# micro_board.net
KiCad netlist of a schematic drawn in EAGLE
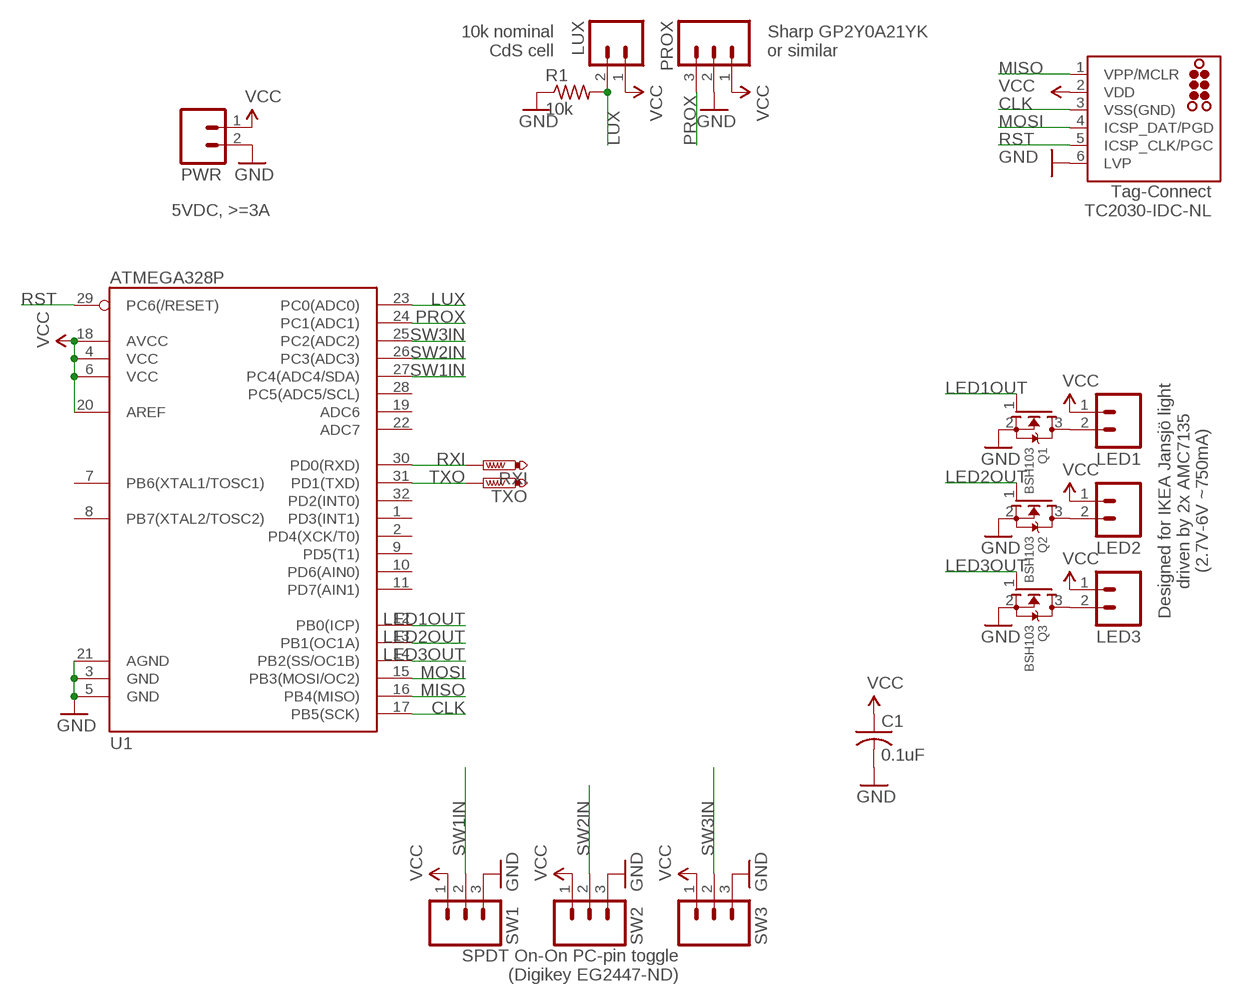
[diagram p0: schematic, sheet 1]

(export (version "E")
  (design (tool "Eeschema 10.0.6"))
  (components
    (comp (ref "C1")
      (value "0.1uF")
      (footprint "eagle-import:C0603")
      (libsource (lib "eagle-import") (part "C-USC0603"))
    )
    (comp (ref "J1")
      (value "TC2030-MCP-NL")
      (footprint "eagle-import:TC2030-MCP-NL")
      (libsource (lib "eagle-import") (part "TC2030-MCP-NL"))
    )
    (comp (ref "LED1")
      (value "M02POLAR_LOCK")
      (footprint "eagle-import:MOLEX-1X2_LOCK")
      (libsource (lib "eagle-import") (part "M02POLAR_LOCK"))
    )
    (comp (ref "LED2")
      (value "M02POLAR_LOCK")
      (footprint "eagle-import:MOLEX-1X2_LOCK")
      (libsource (lib "eagle-import") (part "M02POLAR_LOCK"))
    )
    (comp (ref "LED3")
      (value "M02POLAR_LOCK")
      (footprint "eagle-import:MOLEX-1X2_LOCK")
      (libsource (lib "eagle-import") (part "M02POLAR_LOCK"))
    )
    (comp (ref "LUX")
      (value "M02POLAR_LOCK")
      (footprint "eagle-import:MOLEX-1X2_LOCK")
      (libsource (lib "eagle-import") (part "M02POLAR_LOCK"))
    )
    (comp (ref "PROX")
      (value "M03POLAR_LOCK")
      (footprint "eagle-import:MOLEX-1X3_LOCK")
      (libsource (lib "eagle-import") (part "M03POLAR_LOCK"))
    )
    (comp (ref "PWR")
      (value "M02POLAR_LOCK")
      (footprint "eagle-import:MOLEX-1X2_LOCK")
      (libsource (lib "eagle-import") (part "M02POLAR_LOCK"))
    )
    (comp (ref "Q1")
      (value "BSH103")
      (footprint "eagle-import:SOT23")
      (libsource (lib "eagle-import") (part "MOSFET-NREFLOW"))
    )
    (comp (ref "Q2")
      (value "BSH103")
      (footprint "eagle-import:SOT23")
      (libsource (lib "eagle-import") (part "MOSFET-NREFLOW"))
    )
    (comp (ref "Q3")
      (value "BSH103")
      (footprint "eagle-import:SOT23")
      (libsource (lib "eagle-import") (part "MOSFET-NREFLOW"))
    )
    (comp (ref "R1")
      (value "10k")
      (footprint "eagle-import:R0603")
      (libsource (lib "eagle-import") (part "R-US_R0603"))
    )
    (comp (ref "RXI")
      (value "PTR1B1,27")
      (footprint "eagle-import:B1,27")
      (libsource (lib "eagle-import") (part "PTR1B1,27"))
    )
    (comp (ref "SW1")
      (value "M031X03_NO_SILK")
      (footprint "eagle-import:1X03_NO_SILK")
      (libsource (lib "eagle-import") (part "M031X03_NO_SILK"))
    )
    (comp (ref "SW2")
      (value "M031X03_NO_SILK")
      (footprint "eagle-import:1X03_NO_SILK")
      (libsource (lib "eagle-import") (part "M031X03_NO_SILK"))
    )
    (comp (ref "SW3")
      (value "M031X03_NO_SILK")
      (footprint "eagle-import:1X03_NO_SILK")
      (libsource (lib "eagle-import") (part "M031X03_NO_SILK"))
    )
    (comp (ref "TXO")
      (value "PTR1B1,27")
      (footprint "eagle-import:B1,27")
      (libsource (lib "eagle-import") (part "PTR1B1,27"))
    )
    (comp (ref "U1")
      (value "ATMEGA328P")
      (footprint "eagle-import:TQFP32-08")
      (libsource (lib "eagle-import") (part "ATMEGA328_SMT"))
    )
  )
  (nets
    (net (code "1") (name "/CLK") (class "Default")
      (node (ref "J1") (pin "3") (pinfunction "VSS(GND)_3") (pintype "power_in"))
      (node (ref "U1") (pin "17") (pinfunction "PB5(SCK)_17") (pintype "bidirectional"))
    )
    (net (code "2") (name "/LED1OUT") (class "Default")
      (node (ref "Q1") (pin "1") (pinfunction "G_1") (pintype "bidirectional"))
      (node (ref "U1") (pin "12") (pinfunction "PB0(ICP)_12") (pintype "bidirectional"))
    )
    (net (code "3") (name "/LED2OUT") (class "Default")
      (node (ref "Q2") (pin "1") (pinfunction "G_1") (pintype "bidirectional"))
      (node (ref "U1") (pin "13") (pinfunction "PB1(OC1A)_13") (pintype "bidirectional"))
    )
    (net (code "4") (name "/LED3OUT") (class "Default")
      (node (ref "Q3") (pin "1") (pinfunction "G_1") (pintype "bidirectional"))
      (node (ref "U1") (pin "14") (pinfunction "PB2(SS/OC1B)_14") (pintype "bidirectional"))
    )
    (net (code "5") (name "/LUX") (class "Default")
      (node (ref "LUX") (pin "2") (pinfunction "2_2") (pintype "passive"))
      (node (ref "R1") (pin "2") (pinfunction "2_2") (pintype "passive"))
      (node (ref "U1") (pin "23") (pinfunction "PC0(ADC0)_23") (pintype "bidirectional"))
    )
    (net (code "6") (name "/MISO") (class "Default")
      (node (ref "J1") (pin "1") (pinfunction "VPP/MCLR_1") (pintype "passive"))
      (node (ref "U1") (pin "16") (pinfunction "PB4(MISO)_16") (pintype "bidirectional"))
    )
    (net (code "7") (name "/MOSI") (class "Default")
      (node (ref "J1") (pin "4") (pinfunction "ICSP_DAT/PGD_4") (pintype "bidirectional"))
      (node (ref "U1") (pin "15") (pinfunction "PB3(MOSI/OC2)_15") (pintype "bidirectional"))
    )
    (net (code "8") (name "/PROX") (class "Default")
      (node (ref "PROX") (pin "3") (pinfunction "3_3") (pintype "passive"))
      (node (ref "U1") (pin "24") (pinfunction "PC1(ADC1)_24") (pintype "bidirectional"))
    )
    (net (code "9") (name "/RST") (class "Default")
      (node (ref "J1") (pin "5") (pinfunction "ICSP_CLK/PGC_5") (pintype "output"))
      (node (ref "U1") (pin "29") (pinfunction "PC6(/RESET)_29") (pintype "bidirectional"))
    )
    (net (code "10") (name "/RXI") (class "Default")
      (node (ref "RXI") (pin "TP") (pinfunction "TP_TP") (pintype "input"))
      (node (ref "U1") (pin "30") (pinfunction "PD0(RXD)_30") (pintype "bidirectional"))
    )
    (net (code "11") (name "/SW1IN") (class "Default")
      (node (ref "SW1") (pin "2") (pinfunction "2_2") (pintype "passive"))
      (node (ref "U1") (pin "27") (pinfunction "PC4(ADC4/SDA)_27") (pintype "bidirectional"))
    )
    (net (code "12") (name "/SW2IN") (class "Default")
      (node (ref "SW2") (pin "2") (pinfunction "2_2") (pintype "passive"))
      (node (ref "U1") (pin "26") (pinfunction "PC3(ADC3)_26") (pintype "bidirectional"))
    )
    (net (code "13") (name "/SW3IN") (class "Default")
      (node (ref "SW3") (pin "2") (pinfunction "2_2") (pintype "passive"))
      (node (ref "U1") (pin "25") (pinfunction "PC2(ADC2)_25") (pintype "bidirectional"))
    )
    (net (code "14") (name "/TXO") (class "Default")
      (node (ref "TXO") (pin "TP") (pinfunction "TP_TP") (pintype "input"))
      (node (ref "U1") (pin "31") (pinfunction "PD1(TXD)_31") (pintype "bidirectional"))
    )
    (net (code "15") (name "GND") (class "Default")
      (node (ref "C1") (pin "2") (pinfunction "2_2") (pintype "passive"))
      (node (ref "J1") (pin "6") (pinfunction "LVP_6") (pintype "bidirectional"))
      (node (ref "PROX") (pin "2") (pinfunction "2_2") (pintype "passive"))
      (node (ref "PWR") (pin "2") (pinfunction "2_2") (pintype "passive"))
      (node (ref "Q1") (pin "2") (pinfunction "S_2") (pintype "bidirectional"))
      (node (ref "Q2") (pin "2") (pinfunction "S_2") (pintype "bidirectional"))
      (node (ref "Q3") (pin "2") (pinfunction "S_2") (pintype "bidirectional"))
      (node (ref "R1") (pin "1") (pinfunction "1_1") (pintype "passive"))
      (node (ref "SW1") (pin "3") (pinfunction "3_3") (pintype "passive"))
      (node (ref "SW2") (pin "3") (pinfunction "3_3") (pintype "passive"))
      (node (ref "SW3") (pin "3") (pinfunction "3_3") (pintype "passive"))
      (node (ref "U1") (pin "21") (pinfunction "AGND_21") (pintype "bidirectional"))
      (node (ref "U1") (pin "3") (pinfunction "GND_3") (pintype "bidirectional"))
      (node (ref "U1") (pin "5") (pinfunction "GND_5") (pintype "bidirectional"))
    )
    (net (code "16") (name "Net-(Q1-D)") (class "Default")
      (node (ref "LED1") (pin "2") (pinfunction "2_2") (pintype "passive"))
      (node (ref "Q1") (pin "3") (pinfunction "D_3") (pintype "bidirectional"))
    )
    (net (code "17") (name "Net-(Q2-D)") (class "Default")
      (node (ref "LED2") (pin "2") (pinfunction "2_2") (pintype "passive"))
      (node (ref "Q2") (pin "3") (pinfunction "D_3") (pintype "bidirectional"))
    )
    (net (code "18") (name "Net-(Q3-D)") (class "Default")
      (node (ref "LED3") (pin "2") (pinfunction "2_2") (pintype "passive"))
      (node (ref "Q3") (pin "3") (pinfunction "D_3") (pintype "bidirectional"))
    )
    (net (code "19") (name "VCC") (class "Default")
      (node (ref "C1") (pin "1") (pinfunction "1_1") (pintype "passive"))
      (node (ref "J1") (pin "2") (pinfunction "VDD_2") (pintype "power_in"))
      (node (ref "LED1") (pin "1") (pinfunction "1_1") (pintype "passive"))
      (node (ref "LED2") (pin "1") (pinfunction "1_1") (pintype "passive"))
      (node (ref "LED3") (pin "1") (pinfunction "1_1") (pintype "passive"))
      (node (ref "LUX") (pin "1") (pinfunction "1_1") (pintype "passive"))
      (node (ref "PROX") (pin "1") (pinfunction "1_1") (pintype "passive"))
      (node (ref "PWR") (pin "1") (pinfunction "1_1") (pintype "passive"))
      (node (ref "SW1") (pin "1") (pinfunction "1_1") (pintype "passive"))
      (node (ref "SW2") (pin "1") (pinfunction "1_1") (pintype "passive"))
      (node (ref "SW3") (pin "1") (pinfunction "1_1") (pintype "passive"))
      (node (ref "U1") (pin "18") (pinfunction "AVCC_18") (pintype "bidirectional"))
      (node (ref "U1") (pin "20") (pinfunction "AREF_20") (pintype "bidirectional"))
      (node (ref "U1") (pin "4") (pinfunction "VCC_4") (pintype "bidirectional"))
      (node (ref "U1") (pin "6") (pinfunction "VCC_6") (pintype "bidirectional"))
    )
    (net (code "20") (name "unconnected-(U1-ADC6-Pad19)") (class "Default")
      (node (ref "U1") (pin "19") (pinfunction "ADC6_19") (pintype "bidirectional"))
    )
    (net (code "21") (name "unconnected-(U1-ADC7-Pad22)") (class "Default")
      (node (ref "U1") (pin "22") (pinfunction "ADC7_22") (pintype "bidirectional"))
    )
    (net (code "22") (name "unconnected-(U1-PB6(XTAL1{slash}TOSC1)-Pad7)") (class "Default")
      (node (ref "U1") (pin "7") (pinfunction "PB6(XTAL1/TOSC1)_7") (pintype "bidirectional"))
    )
    (net (code "23") (name "unconnected-(U1-PB7(XTAL2{slash}TOSC2)-Pad8)") (class "Default")
      (node (ref "U1") (pin "8") (pinfunction "PB7(XTAL2/TOSC2)_8") (pintype "bidirectional"))
    )
    (net (code "24") (name "unconnected-(U1-PC5(ADC5{slash}SCL)-Pad28)") (class "Default")
      (node (ref "U1") (pin "28") (pinfunction "PC5(ADC5/SCL)_28") (pintype "bidirectional"))
    )
    (net (code "25") (name "unconnected-(U1-PD2(INT0)-Pad32)") (class "Default")
      (node (ref "U1") (pin "32") (pinfunction "PD2(INT0)_32") (pintype "bidirectional"))
    )
    (net (code "26") (name "unconnected-(U1-PD3(INT1)-Pad1)") (class "Default")
      (node (ref "U1") (pin "1") (pinfunction "PD3(INT1)_1") (pintype "bidirectional"))
    )
    (net (code "27") (name "unconnected-(U1-PD4(XCK{slash}T0)-Pad2)") (class "Default")
      (node (ref "U1") (pin "2") (pinfunction "PD4(XCK/T0)_2") (pintype "bidirectional"))
    )
    (net (code "28") (name "unconnected-(U1-PD5(T1)-Pad9)") (class "Default")
      (node (ref "U1") (pin "9") (pinfunction "PD5(T1)_9") (pintype "bidirectional"))
    )
    (net (code "29") (name "unconnected-(U1-PD6(AIN0)-Pad10)") (class "Default")
      (node (ref "U1") (pin "10") (pinfunction "PD6(AIN0)_10") (pintype "bidirectional"))
    )
    (net (code "30") (name "unconnected-(U1-PD7(AIN1)-Pad11)") (class "Default")
      (node (ref "U1") (pin "11") (pinfunction "PD7(AIN1)_11") (pintype "bidirectional"))
    )
  )
)
